# Screen_v2.net
KiCad netlist of a schematic drawn in EAGLE
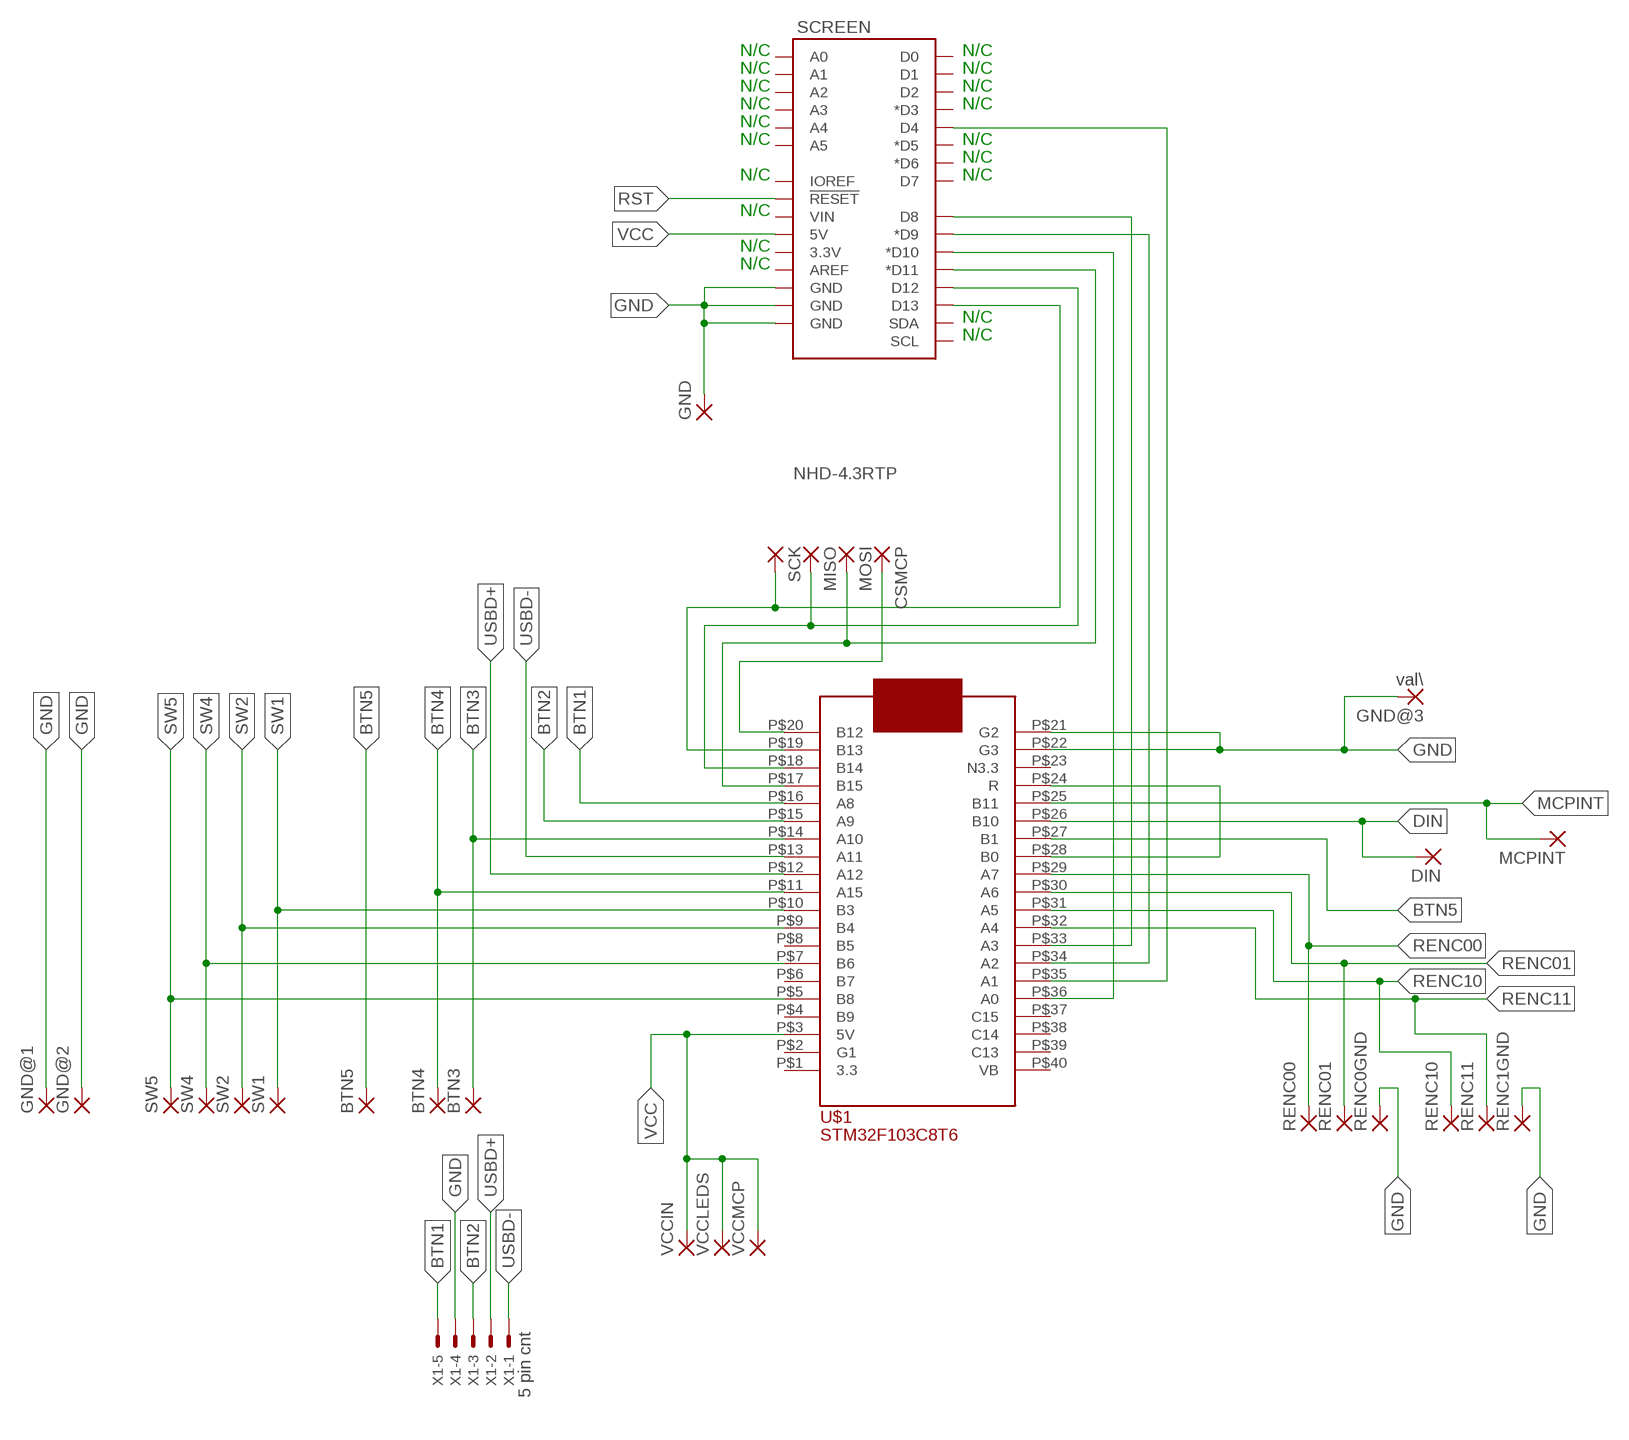
[diagram p0: schematic, sheet 1]

(export (version "E")
  (design (tool "Eeschema 10.0.6"))
  (components
    (comp (ref "BTN3")
      (value "SMD5")
      (footprint "eagle-import:SMD2,54-5,08")
      (libsource (lib "eagle-import") (part "SMD5"))
    )
    (comp (ref "BTN4")
      (value "SMD5")
      (footprint "eagle-import:SMD2,54-5,08")
      (libsource (lib "eagle-import") (part "SMD5"))
    )
    (comp (ref "BTN5")
      (value "SMD5")
      (footprint "eagle-import:SMD2,54-5,08")
      (libsource (lib "eagle-import") (part "SMD5"))
    )
    (comp (ref "CSMCP")
      (value "SMD5")
      (footprint "eagle-import:SMD2,54-5,08")
      (libsource (lib "eagle-import") (part "SMD5"))
    )
    (comp (ref "DIN")
      (value "SMD5")
      (footprint "eagle-import:SMD2,54-5,08")
      (libsource (lib "eagle-import") (part "SMD5"))
    )
    (comp (ref "GND")
      (value "SMD5")
      (footprint "eagle-import:SMD2,54-5,08")
      (libsource (lib "eagle-import") (part "SMD5"))
    )
    (comp (ref "GND@1")
      (value "SMD5")
      (footprint "eagle-import:SMD2,54-5,08")
      (libsource (lib "eagle-import") (part "SMD5"))
    )
    (comp (ref "GND@2")
      (value "SMD5")
      (footprint "eagle-import:SMD2,54-5,08")
      (libsource (lib "eagle-import") (part "SMD5"))
    )
    (comp (ref "GND@3")
      (value "val\\")
      (footprint "eagle-import:SMD2,54-5,08")
      (libsource (lib "eagle-import") (part "SMD5"))
    )
    (comp (ref "MCPINT")
      (value "SMD5")
      (footprint "eagle-import:SMD2,54-5,08")
      (libsource (lib "eagle-import") (part "SMD5"))
    )
    (comp (ref "MISO")
      (value "SMD5")
      (footprint "eagle-import:SMD2,54-5,08")
      (libsource (lib "eagle-import") (part "SMD5"))
    )
    (comp (ref "MOSI")
      (value "SMD5")
      (footprint "eagle-import:SMD2,54-5,08")
      (libsource (lib "eagle-import") (part "SMD5"))
    )
    (comp (ref "RENC00")
      (value "SMD5")
      (footprint "eagle-import:SMD2,54-5,08")
      (libsource (lib "eagle-import") (part "SMD5"))
    )
    (comp (ref "RENC0GND")
      (value "SMD5")
      (footprint "eagle-import:SMD2,54-5,08")
      (libsource (lib "eagle-import") (part "SMD5"))
    )
    (comp (ref "RENC01")
      (value "SMD5")
      (footprint "eagle-import:SMD2,54-5,08")
      (libsource (lib "eagle-import") (part "SMD5"))
    )
    (comp (ref "RENC1GND")
      (value "SMD5")
      (footprint "eagle-import:SMD2,54-5,08")
      (libsource (lib "eagle-import") (part "SMD5"))
    )
    (comp (ref "RENC10")
      (value "SMD5")
      (footprint "eagle-import:SMD2,54-5,08")
      (libsource (lib "eagle-import") (part "SMD5"))
    )
    (comp (ref "RENC11")
      (value "SMD5")
      (footprint "eagle-import:SMD2,54-5,08")
      (libsource (lib "eagle-import") (part "SMD5"))
    )
    (comp (ref "SCK")
      (value "SMD5")
      (footprint "eagle-import:SMD2,54-5,08")
      (libsource (lib "eagle-import") (part "SMD5"))
    )
    (comp (ref "SCREEN")
      (value "NHD-4.3RTP")
      (footprint "eagle-import:NHD-4.3RTP")
      (libsource (lib "eagle-import") (part "NHD-4.3RTP"))
    )
    (comp (ref "SW1")
      (value "SMD5")
      (footprint "eagle-import:SMD2,54-5,08")
      (libsource (lib "eagle-import") (part "SMD5"))
    )
    (comp (ref "SW2")
      (value "SMD5")
      (footprint "eagle-import:SMD2,54-5,08")
      (libsource (lib "eagle-import") (part "SMD5"))
    )
    (comp (ref "SW4")
      (value "SMD5")
      (footprint "eagle-import:SMD2,54-5,08")
      (libsource (lib "eagle-import") (part "SMD5"))
    )
    (comp (ref "SW5")
      (value "SMD5")
      (footprint "eagle-import:SMD2,54-5,08")
      (libsource (lib "eagle-import") (part "SMD5"))
    )
    (comp (ref "U$1")
      (value "STM32F103C8T6DIP40")
      (footprint "eagle-import:STM32")
      (libsource (lib "eagle-import") (part "STM32F103C8T6DIP40"))
    )
    (comp (ref "VCCIN")
      (value "SMD5")
      (footprint "eagle-import:SMD2,54-5,08")
      (libsource (lib "eagle-import") (part "SMD5"))
    )
    (comp (ref "VCCLEDS")
      (value "SMD5")
      (footprint "eagle-import:SMD2,54-5,08")
      (libsource (lib "eagle-import") (part "SMD5"))
    )
    (comp (ref "VCCMCP")
      (value "SMD5")
      (footprint "eagle-import:SMD2,54-5,08")
      (libsource (lib "eagle-import") (part "SMD5"))
    )
    (comp (ref "X1")
      (value "5 pin cnt")
      (footprint "eagle-import:JST-XH-05-PACKAGE-ROUND-PAD")
      (libsource (lib "eagle-import") (part "JST-XH-05-PIN-ROUND-PAD"))
    )
  )
  (nets
    (net (code "1") (name "BTN1") (class "Default")
      (node (ref "U$1") (pin "P$16") (pinfunction "A8_P$16") (pintype "bidirectional"))
      (node (ref "X1") (pin "5") (pinfunction "S_5") (pintype "passive"))
    )
    (net (code "2") (name "BTN2") (class "Default")
      (node (ref "U$1") (pin "P$15") (pinfunction "A9_P$15") (pintype "bidirectional"))
      (node (ref "X1") (pin "3") (pinfunction "S_3") (pintype "passive"))
    )
    (net (code "3") (name "BTN3") (class "Default")
      (node (ref "BTN3") (pin "1") (pinfunction "P_1") (pintype "passive"))
      (node (ref "U$1") (pin "P$14") (pinfunction "A10_P$14") (pintype "bidirectional"))
    )
    (net (code "4") (name "BTN4") (class "Default")
      (node (ref "BTN4") (pin "1") (pinfunction "P_1") (pintype "passive"))
      (node (ref "U$1") (pin "P$11") (pinfunction "A15_P$11") (pintype "bidirectional"))
    )
    (net (code "5") (name "BTN5") (class "Default")
      (node (ref "BTN5") (pin "1") (pinfunction "P_1") (pintype "passive"))
      (node (ref "U$1") (pin "P$27") (pinfunction "B1_P$27") (pintype "bidirectional"))
    )
    (net (code "6") (name "DIN") (class "Default")
      (node (ref "DIN") (pin "1") (pinfunction "P_1") (pintype "passive"))
      (node (ref "U$1") (pin "P$26") (pinfunction "B10_P$26") (pintype "bidirectional"))
    )
    (net (code "7") (name "GND") (class "Default")
      (node (ref "GND") (pin "1") (pinfunction "P_1") (pintype "passive"))
      (node (ref "GND@1") (pin "1") (pinfunction "P_1") (pintype "passive"))
      (node (ref "GND@2") (pin "1") (pinfunction "P_1") (pintype "passive"))
      (node (ref "GND@3") (pin "1") (pinfunction "P_1") (pintype "passive"))
      (node (ref "RENC0GND") (pin "1") (pinfunction "P_1") (pintype "passive"))
      (node (ref "RENC1GND") (pin "1") (pinfunction "P_1") (pintype "passive"))
      (node (ref "SCREEN") (pin "GND@1") (pinfunction "GND_GND@1") (pintype "bidirectional"))
      (node (ref "SCREEN") (pin "GND@2") (pinfunction "GND_GND@2") (pintype "bidirectional"))
      (node (ref "SCREEN") (pin "GND@3") (pinfunction "GND_GND@3") (pintype "bidirectional"))
      (node (ref "U$1") (pin "P$21") (pinfunction "G2_P$21") (pintype "bidirectional"))
      (node (ref "U$1") (pin "P$22") (pinfunction "G3_P$22") (pintype "bidirectional"))
      (node (ref "X1") (pin "4") (pinfunction "S_4") (pintype "passive"))
    )
    (net (code "8") (name "MCPINT") (class "Default")
      (node (ref "MCPINT") (pin "1") (pinfunction "P_1") (pintype "passive"))
      (node (ref "U$1") (pin "P$25") (pinfunction "B11_P$25") (pintype "bidirectional"))
    )
    (net (code "9") (name "Net-(CSMCP-P)") (class "Default")
      (node (ref "CSMCP") (pin "1") (pinfunction "P_1") (pintype "passive"))
      (node (ref "U$1") (pin "P$20") (pinfunction "B12_P$20") (pintype "bidirectional"))
    )
    (net (code "10") (name "Net-(MISO-P)") (class "Default")
      (node (ref "MISO") (pin "1") (pinfunction "P_1") (pintype "passive"))
      (node (ref "SCREEN") (pin "D12") (pinfunction "D12_D12") (pintype "bidirectional"))
      (node (ref "U$1") (pin "P$18") (pinfunction "B14_P$18") (pintype "bidirectional"))
    )
    (net (code "11") (name "Net-(MOSI-P)") (class "Default")
      (node (ref "MOSI") (pin "1") (pinfunction "P_1") (pintype "passive"))
      (node (ref "SCREEN") (pin "D11") (pinfunction "*D11_D11") (pintype "bidirectional"))
      (node (ref "U$1") (pin "P$17") (pinfunction "B15_P$17") (pintype "bidirectional"))
    )
    (net (code "12") (name "Net-(SCK-P)") (class "Default")
      (node (ref "SCK") (pin "1") (pinfunction "P_1") (pintype "passive"))
      (node (ref "SCREEN") (pin "D13") (pinfunction "D13_D13") (pintype "bidirectional"))
      (node (ref "U$1") (pin "P$19") (pinfunction "B13_P$19") (pintype "bidirectional"))
    )
    (net (code "13") (name "Net-(SCREEN-*D9)") (class "Default")
      (node (ref "SCREEN") (pin "D9") (pinfunction "*D9_D9") (pintype "bidirectional"))
      (node (ref "U$1") (pin "P$34") (pinfunction "A2_P$34") (pintype "bidirectional"))
    )
    (net (code "14") (name "Net-(SCREEN-*D10)") (class "Default")
      (node (ref "SCREEN") (pin "D10") (pinfunction "*D10_D10") (pintype "bidirectional"))
      (node (ref "U$1") (pin "P$36") (pinfunction "A0_P$36") (pintype "bidirectional"))
    )
    (net (code "15") (name "Net-(U$1-A1)") (class "Default")
      (node (ref "SCREEN") (pin "D4") (pinfunction "D4_D4") (pintype "bidirectional"))
      (node (ref "U$1") (pin "P$35") (pinfunction "A1_P$35") (pintype "bidirectional"))
    )
    (net (code "16") (name "Net-(U$1-A3)") (class "Default")
      (node (ref "SCREEN") (pin "D8") (pinfunction "D8_D8") (pintype "bidirectional"))
      (node (ref "U$1") (pin "P$33") (pinfunction "A3_P$33") (pintype "bidirectional"))
    )
    (net (code "17") (name "Net-(U$1-B0)") (class "Default")
      (node (ref "U$1") (pin "P$24") (pinfunction "R_P$24") (pintype "bidirectional"))
      (node (ref "U$1") (pin "P$28") (pinfunction "B0_P$28") (pintype "bidirectional"))
    )
    (net (code "18") (name "RENC00") (class "Default")
      (node (ref "RENC00") (pin "1") (pinfunction "P_1") (pintype "passive"))
      (node (ref "U$1") (pin "P$29") (pinfunction "A7_P$29") (pintype "bidirectional"))
    )
    (net (code "19") (name "RENC01") (class "Default")
      (node (ref "RENC01") (pin "1") (pinfunction "P_1") (pintype "passive"))
      (node (ref "U$1") (pin "P$30") (pinfunction "A6_P$30") (pintype "bidirectional"))
    )
    (net (code "20") (name "RENC10") (class "Default")
      (node (ref "RENC10") (pin "1") (pinfunction "P_1") (pintype "passive"))
      (node (ref "U$1") (pin "P$31") (pinfunction "A5_P$31") (pintype "bidirectional"))
    )
    (net (code "21") (name "RENC11") (class "Default")
      (node (ref "RENC11") (pin "1") (pinfunction "P_1") (pintype "passive"))
      (node (ref "U$1") (pin "P$32") (pinfunction "A4_P$32") (pintype "bidirectional"))
    )
    (net (code "22") (name "RST") (class "Default")
      (node (ref "SCREEN") (pin "RESET@1") (pinfunction "~{RESET}_RESET@1") (pintype "bidirectional"))
    )
    (net (code "23") (name "SW1") (class "Default")
      (node (ref "SW1") (pin "1") (pinfunction "P_1") (pintype "passive"))
      (node (ref "U$1") (pin "P$10") (pinfunction "B3_P$10") (pintype "bidirectional"))
    )
    (net (code "24") (name "SW2") (class "Default")
      (node (ref "SW2") (pin "1") (pinfunction "P_1") (pintype "passive"))
      (node (ref "U$1") (pin "P$9") (pinfunction "B4_P$9") (pintype "bidirectional"))
    )
    (net (code "25") (name "SW4") (class "Default")
      (node (ref "SW4") (pin "1") (pinfunction "P_1") (pintype "passive"))
      (node (ref "U$1") (pin "P$7") (pinfunction "B6_P$7") (pintype "bidirectional"))
    )
    (net (code "26") (name "SW5") (class "Default")
      (node (ref "SW5") (pin "1") (pinfunction "P_1") (pintype "passive"))
      (node (ref "U$1") (pin "P$5") (pinfunction "B8_P$5") (pintype "bidirectional"))
    )
    (net (code "27") (name "USBD+") (class "Default")
      (node (ref "U$1") (pin "P$12") (pinfunction "A12_P$12") (pintype "bidirectional"))
      (node (ref "X1") (pin "2") (pinfunction "S_2") (pintype "passive"))
    )
    (net (code "28") (name "USBD-") (class "Default")
      (node (ref "U$1") (pin "P$13") (pinfunction "A11_P$13") (pintype "bidirectional"))
      (node (ref "X1") (pin "1") (pinfunction "S_1") (pintype "passive"))
    )
    (net (code "29") (name "VCC") (class "Default")
      (node (ref "SCREEN") (pin "5V") (pinfunction "5V_5V") (pintype "bidirectional"))
      (node (ref "U$1") (pin "P$3") (pinfunction "5V_P$3") (pintype "bidirectional"))
      (node (ref "VCCIN") (pin "1") (pinfunction "P_1") (pintype "passive"))
      (node (ref "VCCLEDS") (pin "1") (pinfunction "P_1") (pintype "passive"))
      (node (ref "VCCMCP") (pin "1") (pinfunction "P_1") (pintype "passive"))
    )
    (net (code "30") (name "unconnected-(SCREEN-*D3-PadD3)") (class "Default")
      (node (ref "SCREEN") (pin "D3") (pinfunction "*D3_D3") (pintype "bidirectional"))
    )
    (net (code "31") (name "unconnected-(SCREEN-*D5-PadD5)") (class "Default")
      (node (ref "SCREEN") (pin "D5") (pinfunction "*D5_D5") (pintype "bidirectional"))
    )
    (net (code "32") (name "unconnected-(SCREEN-*D6-PadD6)") (class "Default")
      (node (ref "SCREEN") (pin "D6") (pinfunction "*D6_D6") (pintype "bidirectional"))
    )
    (net (code "33") (name "unconnected-(SCREEN-Pad3.3V)") (class "Default")
      (node (ref "SCREEN") (pin "3.3V") (pinfunction "3.3V_3.3V") (pintype "bidirectional"))
    )
    (net (code "34") (name "unconnected-(SCREEN-PadA0)") (class "Default")
      (node (ref "SCREEN") (pin "A0") (pinfunction "A0_A0") (pintype "bidirectional"))
    )
    (net (code "35") (name "unconnected-(SCREEN-PadA1)") (class "Default")
      (node (ref "SCREEN") (pin "A1") (pinfunction "A1_A1") (pintype "bidirectional"))
    )
    (net (code "36") (name "unconnected-(SCREEN-PadA2)") (class "Default")
      (node (ref "SCREEN") (pin "A2") (pinfunction "A2_A2") (pintype "bidirectional"))
    )
    (net (code "37") (name "unconnected-(SCREEN-PadA3)") (class "Default")
      (node (ref "SCREEN") (pin "A3") (pinfunction "A3_A3") (pintype "bidirectional"))
    )
    (net (code "38") (name "unconnected-(SCREEN-PadA4)") (class "Default")
      (node (ref "SCREEN") (pin "A4") (pinfunction "A4_A4") (pintype "bidirectional"))
    )
    (net (code "39") (name "unconnected-(SCREEN-PadA5)") (class "Default")
      (node (ref "SCREEN") (pin "A5") (pinfunction "A5_A5") (pintype "bidirectional"))
    )
    (net (code "40") (name "unconnected-(SCREEN-PadAREF)") (class "Default")
      (node (ref "SCREEN") (pin "AREF") (pinfunction "AREF_AREF") (pintype "bidirectional"))
    )
    (net (code "41") (name "unconnected-(SCREEN-PadD0)") (class "Default")
      (node (ref "SCREEN") (pin "D0") (pinfunction "D0_D0") (pintype "bidirectional"))
    )
    (net (code "42") (name "unconnected-(SCREEN-PadD1)") (class "Default")
      (node (ref "SCREEN") (pin "D1") (pinfunction "D1_D1") (pintype "bidirectional"))
    )
    (net (code "43") (name "unconnected-(SCREEN-PadD2)") (class "Default")
      (node (ref "SCREEN") (pin "D2") (pinfunction "D2_D2") (pintype "bidirectional"))
    )
    (net (code "44") (name "unconnected-(SCREEN-PadD7)") (class "Default")
      (node (ref "SCREEN") (pin "D7") (pinfunction "D7_D7") (pintype "bidirectional"))
    )
    (net (code "45") (name "unconnected-(SCREEN-PadIOREF)") (class "Default")
      (node (ref "SCREEN") (pin "IOREF") (pinfunction "IOREF_IOREF") (pintype "bidirectional"))
    )
    (net (code "46") (name "unconnected-(SCREEN-PadSCL)") (class "Default")
      (node (ref "SCREEN") (pin "SCL") (pinfunction "SCL_SCL") (pintype "bidirectional"))
    )
    (net (code "47") (name "unconnected-(SCREEN-PadSDA)") (class "Default")
      (node (ref "SCREEN") (pin "SDA") (pinfunction "SDA_SDA") (pintype "bidirectional"))
    )
    (net (code "48") (name "unconnected-(SCREEN-PadVIN)") (class "Default")
      (node (ref "SCREEN") (pin "VIN") (pinfunction "VIN_VIN") (pintype "bidirectional"))
    )
    (net (code "49") (name "unconnected-(U$1-3.3-PadP$1)") (class "Default")
      (node (ref "U$1") (pin "P$1") (pinfunction "3.3_P$1") (pintype "bidirectional"))
    )
    (net (code "50") (name "unconnected-(U$1-B5-PadP$8)") (class "Default")
      (node (ref "U$1") (pin "P$8") (pinfunction "B5_P$8") (pintype "bidirectional"))
    )
    (net (code "51") (name "unconnected-(U$1-B7-PadP$6)") (class "Default")
      (node (ref "U$1") (pin "P$6") (pinfunction "B7_P$6") (pintype "bidirectional"))
    )
    (net (code "52") (name "unconnected-(U$1-B9-PadP$4)") (class "Default")
      (node (ref "U$1") (pin "P$4") (pinfunction "B9_P$4") (pintype "bidirectional"))
    )
    (net (code "53") (name "unconnected-(U$1-C13-PadP$39)") (class "Default")
      (node (ref "U$1") (pin "P$39") (pinfunction "C13_P$39") (pintype "bidirectional"))
    )
    (net (code "54") (name "unconnected-(U$1-C14-PadP$38)") (class "Default")
      (node (ref "U$1") (pin "P$38") (pinfunction "C14_P$38") (pintype "bidirectional"))
    )
    (net (code "55") (name "unconnected-(U$1-C15-PadP$37)") (class "Default")
      (node (ref "U$1") (pin "P$37") (pinfunction "C15_P$37") (pintype "bidirectional"))
    )
    (net (code "56") (name "unconnected-(U$1-G1-PadP$2)") (class "Default")
      (node (ref "U$1") (pin "P$2") (pinfunction "G1_P$2") (pintype "bidirectional"))
    )
    (net (code "57") (name "unconnected-(U$1-N3.3-PadP$23)") (class "Default")
      (node (ref "U$1") (pin "P$23") (pinfunction "N3.3_P$23") (pintype "bidirectional"))
    )
    (net (code "58") (name "unconnected-(U$1-VB-PadP$40)") (class "Default")
      (node (ref "U$1") (pin "P$40") (pinfunction "VB_P$40") (pintype "bidirectional"))
    )
  )
)
